# Fuente_TP1.net
KiCad netlist of a schematic drawn in Altium Designer
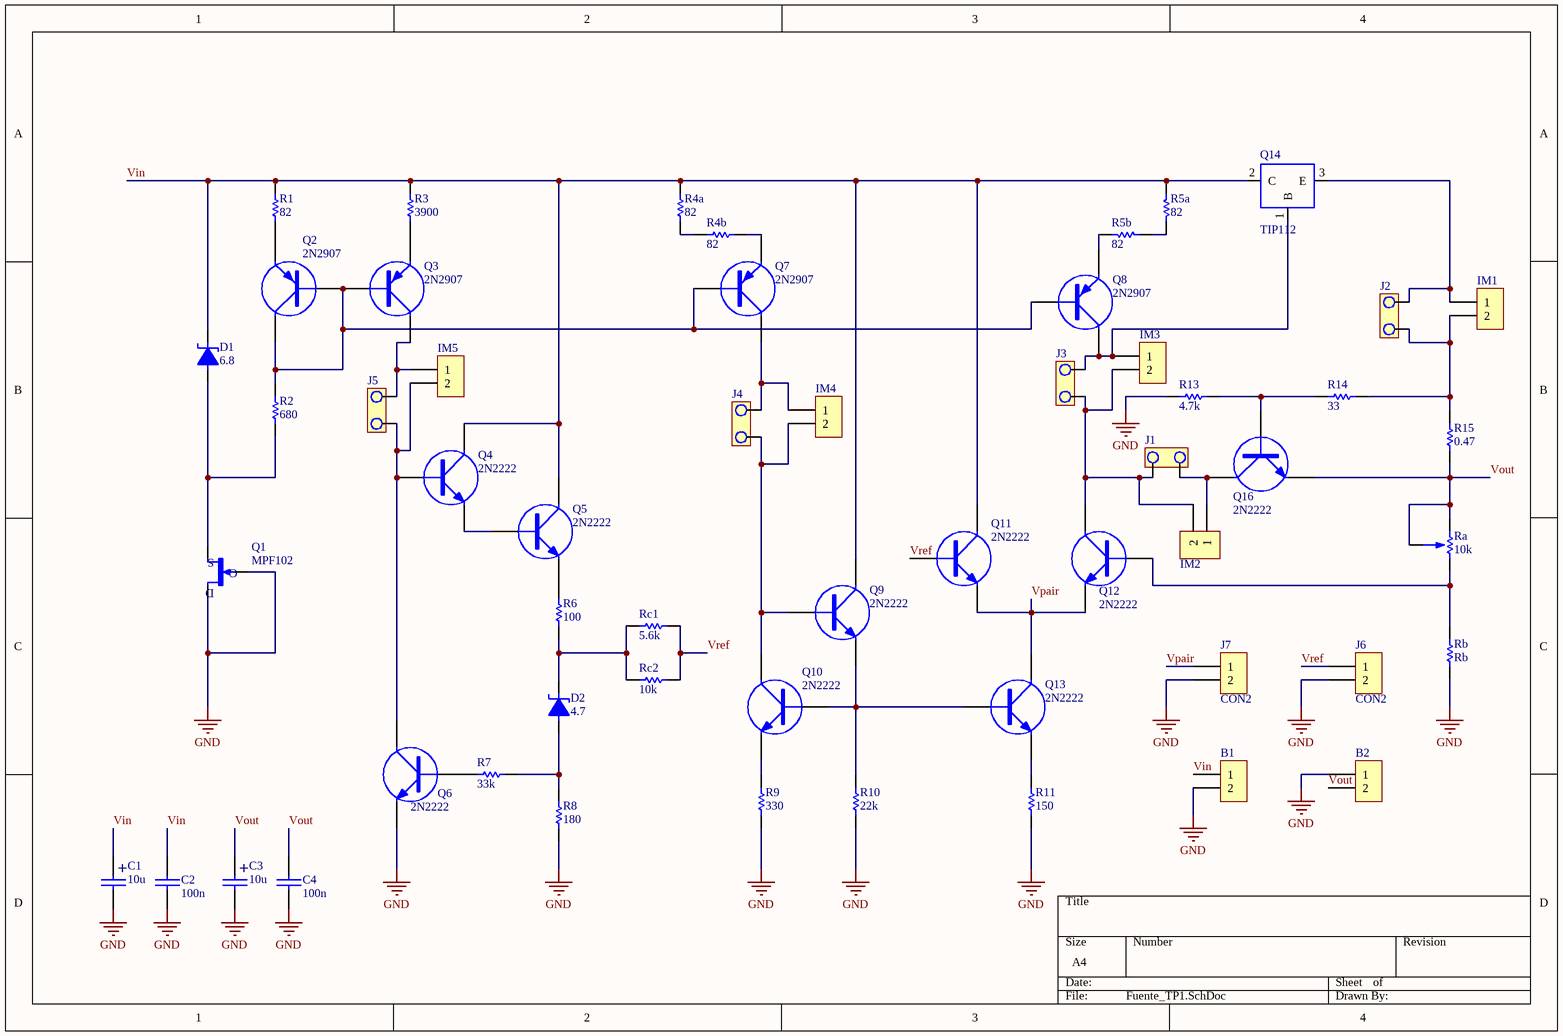
[diagram p0: Fuente_TP1.SchDoc]

(export (version "E")
  (design (tool "Eeschema 10.0.6"))
  (components
    (comp (ref "B1") (value "~") (footprint "BORNERA2") (libsource (lib "Schematics") (part "BORNERA 2")))
    (comp (ref "B2") (value "~") (footprint "BORNERA2") (libsource (lib "Schematics") (part "BORNERA 2")))
    (comp (ref "C1") (value "10u") (footprint "CAP100RP") (libsource (lib "Schematics") (part "CAPPOL")))
    (comp (ref "C2") (value "100n") (footprint "CAP200") (libsource (lib "Schematics") (part "CAP")))
    (comp (ref "C3") (value "10u") (footprint "CAP100RP") (libsource (lib "Schematics") (part "CAPPOL")))
    (comp (ref "C4") (value "100n") (footprint "CAP200") (libsource (lib "Schematics") (part "CAP")))
    (comp (ref "D1") (value "6.8") (footprint "DO41") (libsource (lib "Schematics") (part "DIODO ZENER")))
    (comp (ref "D2") (value "4.7") (footprint "DO41") (libsource (lib "Schematics") (part "DIODO ZENER")))
    (comp (ref "IM1") (value "~") (footprint "SIP2") (libsource (lib "Schematics") (part "CON2")))
    (comp (ref "IM2") (value "~") (footprint "SIP2") (libsource (lib "") (part "CON2_1")))
    (comp (ref "IM3") (value "~") (footprint "SIP2") (libsource (lib "Schematics") (part "CON2")))
    (comp (ref "IM4") (value "~") (footprint "SIP2") (libsource (lib "Schematics") (part "CON2")))
    (comp (ref "IM5") (value "~") (footprint "SIP2") (libsource (lib "Schematics") (part "CON2")))
    (comp (ref "J1") (value "~") (footprint "JUMPER2") (libsource (lib "Schematics") (part "JUMPER")))
    (comp (ref "J2") (value "~") (footprint "JUMPER2") (libsource (lib "") (part "JUMPER_1")))
    (comp (ref "J3") (value "~") (footprint "JUMPER2") (libsource (lib "") (part "JUMPER_1")))
    (comp (ref "J4") (value "~") (footprint "JUMPER2") (libsource (lib "") (part "JUMPER_1")))
    (comp (ref "J5") (value "~") (footprint "JUMPER2") (libsource (lib "") (part "JUMPER_1")))
    (comp (ref "J6") (value "CON2") (footprint "SIP2") (libsource (lib "Schematics") (part "CON2")))
    (comp (ref "J7") (value "CON2") (footprint "SIP2") (libsource (lib "Schematics") (part "CON2")))
    (comp (ref "Q1")
      (value "MPF102")
      (footprint "Footprints:TO92")
      (description "RF Mosfet N-Channel JFET TO-92-3")
      (fields (field (name "MF") "ON Semiconductor"))
      (libsource (lib "Schematics") (part "MPF102"))
    )
    (comp (ref "Q2")
      (value "2N2907")
      (footprint "TO92")
      (libsource (lib "Schematics") (part "TRANSISTOR PNP"))
    )
    (comp (ref "Q3")
      (value "2N2907")
      (footprint "TO92")
      (libsource (lib "Schematics") (part "TRANSISTOR PNP"))
    )
    (comp (ref "Q4") (value "2N2222") (footprint "TO92") (libsource (lib "Schematics") (part "2N2222")))
    (comp (ref "Q5") (value "2N2222") (footprint "TO92") (libsource (lib "Schematics") (part "2N2222")))
    (comp (ref "Q6") (value "2N2222") (footprint "TO92") (libsource (lib "Schematics") (part "2N2222")))
    (comp (ref "Q7")
      (value "2N2907")
      (footprint "TO92")
      (libsource (lib "Schematics") (part "TRANSISTOR PNP"))
    )
    (comp (ref "Q8")
      (value "2N2907")
      (footprint "TO92")
      (libsource (lib "Schematics") (part "TRANSISTOR PNP"))
    )
    (comp (ref "Q9") (value "2N2222") (footprint "TO92") (libsource (lib "Schematics") (part "2N2222")))
    (comp (ref "Q10") (value "2N2222") (footprint "TO92") (libsource (lib "Schematics") (part "2N2222")))
    (comp (ref "Q11") (value "2N2222") (footprint "TO92") (libsource (lib "Schematics") (part "2N2222")))
    (comp (ref "Q12") (value "2N2222") (footprint "TO92") (libsource (lib "Schematics") (part "2N2222")))
    (comp (ref "Q13") (value "2N2222") (footprint "TO92") (libsource (lib "Schematics") (part "2N2222")))
    (comp (ref "Q14")
      (value "TIP112")
      (footprint "Footprints:TO-220 V")
      (libsource (lib "Schematics") (part "TIP112"))
    )
    (comp (ref "Q16") (value "2N2222") (footprint "TO92") (libsource (lib "Schematics") (part "2N2222")))
    (comp (ref "R1") (value "82") (footprint "0805") (libsource (lib "Schematics") (part "RES")))
    (comp (ref "R2") (value "680") (footprint "0805") (libsource (lib "Schematics") (part "RES")))
    (comp (ref "R3") (value "3900") (footprint "0805") (libsource (lib "Schematics") (part "RES")))
    (comp (ref "R4a") (value "82") (footprint "0805") (libsource (lib "Schematics") (part "RES")))
    (comp (ref "R4b") (value "82") (footprint "0805") (libsource (lib "Schematics") (part "RES")))
    (comp (ref "R5a") (value "82") (footprint "0805") (libsource (lib "Schematics") (part "RES")))
    (comp (ref "R5b") (value "82") (footprint "0805") (libsource (lib "Schematics") (part "RES")))
    (comp (ref "R6") (value "100") (footprint "RES300") (libsource (lib "Schematics") (part "RES")))
    (comp (ref "R7") (value "33k") (footprint "0805") (libsource (lib "Schematics") (part "RES")))
    (comp (ref "R8") (value "180") (footprint "RES300") (libsource (lib "Schematics") (part "RES")))
    (comp (ref "R9") (value "330") (footprint "0805") (libsource (lib "Schematics") (part "RES")))
    (comp (ref "R10") (value "22k") (footprint "0805") (libsource (lib "Schematics") (part "RES")))
    (comp (ref "R11") (value "150") (footprint "0805") (libsource (lib "Schematics") (part "RES")))
    (comp (ref "R13") (value "4.7k") (footprint "0805") (libsource (lib "Schematics") (part "RES")))
    (comp (ref "R14") (value "33") (footprint "0805") (libsource (lib "Schematics") (part "RES")))
    (comp (ref "R15") (value "0.47") (footprint "RES600") (libsource (lib "Schematics") (part "RES")))
    (comp (ref "Ra") (value "10k") (footprint "PRESET V") (libsource (lib "Schematics") (part "PRESET")))
    (comp (ref "Rb") (value "Rb") (footprint "0805") (libsource (lib "Schematics") (part "RES")))
    (comp (ref "Rc1") (value "5.6k") (footprint "0805") (libsource (lib "Schematics") (part "RES")))
    (comp (ref "Rc2") (value "10k") (footprint "0805") (libsource (lib "Schematics") (part "RES")))
  )
  (nets
    (net (code "1") (name "/Vin") (class "Default")
      (node (ref "B1") (pin "1") (pinfunction "1_1") (pintype "passive"))
      (node (ref "C1") (pin "1") (pinfunction "1_1") (pintype "passive"))
      (node (ref "C2") (pin "1") (pinfunction "1_1") (pintype "passive"))
      (node (ref "D1") (pin "2") (pinfunction "2_2") (pintype "passive"))
      (node (ref "Q11") (pin "3") (pinfunction "C_3") (pintype "passive"))
      (node (ref "Q14") (pin "2") (pinfunction "C_2") (pintype "bidirectional"))
      (node (ref "Q4") (pin "3") (pinfunction "C_3") (pintype "passive"))
      (node (ref "Q5") (pin "3") (pinfunction "C_3") (pintype "passive"))
      (node (ref "Q9") (pin "3") (pinfunction "C_3") (pintype "passive"))
      (node (ref "R1") (pin "2") (pinfunction "2_2") (pintype "passive"))
      (node (ref "R3") (pin "2") (pinfunction "2_2") (pintype "passive"))
      (node (ref "R4a") (pin "1") (pinfunction "1_1") (pintype "passive"))
      (node (ref "R5a") (pin "1") (pinfunction "1_1") (pintype "passive"))
    )
    (net (code "2") (name "/Vout") (class "Default")
      (node (ref "B2") (pin "2") (pinfunction "2_2") (pintype "passive"))
      (node (ref "C3") (pin "1") (pinfunction "1_1") (pintype "passive"))
      (node (ref "C4") (pin "1") (pinfunction "1_1") (pintype "passive"))
      (node (ref "Q16") (pin "2") (pinfunction "E_2") (pintype "passive"))
      (node (ref "R15") (pin "1") (pinfunction "1_1") (pintype "passive"))
      (node (ref "Ra") (pin "2") (pinfunction "2_2") (pintype "passive"))
      (node (ref "Ra") (pin "3") (pinfunction "3_3") (pintype "passive"))
    )
    (net (code "3") (name "/Vpair") (class "Default")
      (node (ref "J7") (pin "1") (pinfunction "1_1") (pintype "passive"))
      (node (ref "Q11") (pin "2") (pinfunction "E_2") (pintype "passive"))
      (node (ref "Q12") (pin "2") (pinfunction "E_2") (pintype "passive"))
      (node (ref "Q13") (pin "3") (pinfunction "C_3") (pintype "passive"))
    )
    (net (code "4") (name "/Vref") (class "Default")
      (node (ref "J6") (pin "1") (pinfunction "1_1") (pintype "passive"))
      (node (ref "Q11") (pin "1") (pinfunction "B_1") (pintype "passive"))
      (node (ref "Rc1") (pin "1") (pinfunction "1_1") (pintype "passive"))
      (node (ref "Rc2") (pin "1") (pinfunction "1_1") (pintype "passive"))
    )
    (net (code "5") (name "GND") (class "Default")
      (node (ref "B1") (pin "2") (pinfunction "2_2") (pintype "passive"))
      (node (ref "B2") (pin "1") (pinfunction "1_1") (pintype "passive"))
      (node (ref "C1") (pin "2") (pinfunction "2_2") (pintype "passive"))
      (node (ref "C2") (pin "2") (pinfunction "2_2") (pintype "passive"))
      (node (ref "C3") (pin "2") (pinfunction "2_2") (pintype "passive"))
      (node (ref "C4") (pin "2") (pinfunction "2_2") (pintype "passive"))
      (node (ref "J6") (pin "2") (pinfunction "2_2") (pintype "passive"))
      (node (ref "J7") (pin "2") (pinfunction "2_2") (pintype "passive"))
      (node (ref "Q1") (pin "1") (pinfunction "D_1") (pintype "passive"))
      (node (ref "Q1") (pin "3") (pinfunction "G_3") (pintype "passive"))
      (node (ref "Q6") (pin "2") (pinfunction "E_2") (pintype "passive"))
      (node (ref "R10") (pin "2") (pinfunction "2_2") (pintype "passive"))
      (node (ref "R11") (pin "2") (pinfunction "2_2") (pintype "passive"))
      (node (ref "R13") (pin "2") (pinfunction "2_2") (pintype "passive"))
      (node (ref "R8") (pin "2") (pinfunction "2_2") (pintype "passive"))
      (node (ref "R9") (pin "2") (pinfunction "2_2") (pintype "passive"))
      (node (ref "Rb") (pin "1") (pinfunction "1_1") (pintype "passive"))
    )
    (net (code "6") (name "Net-(D2-Pad1)") (class "Default")
      (node (ref "D2") (pin "1") (pinfunction "1_1") (pintype "passive"))
      (node (ref "R7") (pin "1") (pinfunction "1_1") (pintype "passive"))
      (node (ref "R8") (pin "1") (pinfunction "1_1") (pintype "passive"))
    )
    (net (code "7") (name "Net-(D2-Pad2)") (class "Default")
      (node (ref "D2") (pin "2") (pinfunction "2_2") (pintype "passive"))
      (node (ref "R6") (pin "1") (pinfunction "1_1") (pintype "passive"))
      (node (ref "Rc1") (pin "2") (pinfunction "2_2") (pintype "passive"))
      (node (ref "Rc2") (pin "2") (pinfunction "2_2") (pintype "passive"))
    )
    (net (code "8") (name "Net-(IM1-Pad2)") (class "Default")
      (node (ref "IM1") (pin "2") (pinfunction "2_2") (pintype "passive"))
      (node (ref "J2") (pin "2") (pinfunction "2_2") (pintype "passive"))
      (node (ref "R14") (pin "1") (pinfunction "1_1") (pintype "passive"))
      (node (ref "R15") (pin "2") (pinfunction "2_2") (pintype "passive"))
    )
    (net (code "9") (name "Net-(Q1-S)") (class "Default")
      (node (ref "D1") (pin "1") (pinfunction "1_1") (pintype "passive"))
      (node (ref "Q1") (pin "2") (pinfunction "S_2") (pintype "passive"))
      (node (ref "R2") (pin "1") (pinfunction "1_1") (pintype "passive"))
    )
    (net (code "10") (name "Net-(Q2-B)") (class "Default")
      (node (ref "Q2") (pin "1") (pinfunction "B_1") (pintype "passive"))
      (node (ref "Q2") (pin "2") (pinfunction "C_2") (pintype "passive"))
      (node (ref "Q3") (pin "1") (pinfunction "B_1") (pintype "passive"))
      (node (ref "Q7") (pin "1") (pinfunction "B_1") (pintype "passive"))
      (node (ref "Q8") (pin "1") (pinfunction "B_1") (pintype "passive"))
      (node (ref "R2") (pin "2") (pinfunction "2_2") (pintype "passive"))
    )
    (net (code "11") (name "Net-(Q2-E)") (class "Default")
      (node (ref "Q2") (pin "3") (pinfunction "E_3") (pintype "passive"))
      (node (ref "R1") (pin "1") (pinfunction "1_1") (pintype "passive"))
    )
    (net (code "12") (name "Net-(Q3-C)") (class "Default")
      (node (ref "IM5") (pin "1") (pinfunction "1_1") (pintype "passive"))
      (node (ref "J5") (pin "1") (pinfunction "1_1") (pintype "passive"))
      (node (ref "Q3") (pin "2") (pinfunction "C_2") (pintype "passive"))
    )
    (net (code "13") (name "Net-(Q3-E)") (class "Default")
      (node (ref "Q3") (pin "3") (pinfunction "E_3") (pintype "passive"))
      (node (ref "R3") (pin "1") (pinfunction "1_1") (pintype "passive"))
    )
    (net (code "14") (name "Net-(Q4-B)") (class "Default")
      (node (ref "IM5") (pin "2") (pinfunction "2_2") (pintype "passive"))
      (node (ref "J5") (pin "2") (pinfunction "2_2") (pintype "passive"))
      (node (ref "Q4") (pin "1") (pinfunction "B_1") (pintype "passive"))
      (node (ref "Q6") (pin "3") (pinfunction "C_3") (pintype "passive"))
    )
    (net (code "15") (name "Net-(Q4-E)") (class "Default")
      (node (ref "Q4") (pin "2") (pinfunction "E_2") (pintype "passive"))
      (node (ref "Q5") (pin "1") (pinfunction "B_1") (pintype "passive"))
    )
    (net (code "16") (name "Net-(Q5-E)") (class "Default")
      (node (ref "Q5") (pin "2") (pinfunction "E_2") (pintype "passive"))
      (node (ref "R6") (pin "2") (pinfunction "2_2") (pintype "passive"))
    )
    (net (code "17") (name "Net-(Q6-B)") (class "Default")
      (node (ref "Q6") (pin "1") (pinfunction "B_1") (pintype "passive"))
      (node (ref "R7") (pin "2") (pinfunction "2_2") (pintype "passive"))
    )
    (net (code "18") (name "Net-(Q7-C)") (class "Default")
      (node (ref "IM4") (pin "1") (pinfunction "1_1") (pintype "passive"))
      (node (ref "J4") (pin "1") (pinfunction "1_1") (pintype "passive"))
      (node (ref "Q7") (pin "2") (pinfunction "C_2") (pintype "passive"))
    )
    (net (code "19") (name "Net-(Q7-E)") (class "Default")
      (node (ref "Q7") (pin "3") (pinfunction "E_3") (pintype "passive"))
      (node (ref "R4b") (pin "1") (pinfunction "1_1") (pintype "passive"))
    )
    (net (code "20") (name "Net-(Q8-E)") (class "Default")
      (node (ref "Q8") (pin "3") (pinfunction "E_3") (pintype "passive"))
      (node (ref "R5b") (pin "1") (pinfunction "1_1") (pintype "passive"))
    )
    (net (code "21") (name "Net-(Q10-B)") (class "Default")
      (node (ref "Q10") (pin "1") (pinfunction "B_1") (pintype "passive"))
      (node (ref "Q13") (pin "1") (pinfunction "B_1") (pintype "passive"))
      (node (ref "Q9") (pin "2") (pinfunction "E_2") (pintype "passive"))
      (node (ref "R10") (pin "1") (pinfunction "1_1") (pintype "passive"))
    )
    (net (code "22") (name "Net-(Q10-C)") (class "Default")
      (node (ref "IM4") (pin "2") (pinfunction "2_2") (pintype "passive"))
      (node (ref "J4") (pin "2") (pinfunction "2_2") (pintype "passive"))
      (node (ref "Q10") (pin "3") (pinfunction "C_3") (pintype "passive"))
      (node (ref "Q9") (pin "1") (pinfunction "B_1") (pintype "passive"))
    )
    (net (code "23") (name "Net-(Q10-E)") (class "Default")
      (node (ref "Q10") (pin "2") (pinfunction "E_2") (pintype "passive"))
      (node (ref "R9") (pin "1") (pinfunction "1_1") (pintype "passive"))
    )
    (net (code "24") (name "Net-(Q12-B)") (class "Default")
      (node (ref "Q12") (pin "1") (pinfunction "B_1") (pintype "passive"))
      (node (ref "Ra") (pin "1") (pinfunction "1_1") (pintype "passive"))
      (node (ref "Rb") (pin "2") (pinfunction "2_2") (pintype "passive"))
    )
    (net (code "25") (name "Net-(Q12-C)") (class "Default")
      (node (ref "IM2") (pin "2") (pinfunction "2_2") (pintype "passive"))
      (node (ref "IM3") (pin "2") (pinfunction "2_2") (pintype "passive"))
      (node (ref "J1") (pin "2") (pinfunction "2_2") (pintype "passive"))
      (node (ref "J3") (pin "2") (pinfunction "2_2") (pintype "passive"))
      (node (ref "Q12") (pin "3") (pinfunction "C_3") (pintype "passive"))
    )
    (net (code "26") (name "Net-(Q13-E)") (class "Default")
      (node (ref "Q13") (pin "2") (pinfunction "E_2") (pintype "passive"))
      (node (ref "R11") (pin "1") (pinfunction "1_1") (pintype "passive"))
    )
    (net (code "27") (name "Net-(Q14-B)") (class "Default")
      (node (ref "IM3") (pin "1") (pinfunction "1_1") (pintype "passive"))
      (node (ref "J3") (pin "1") (pinfunction "1_1") (pintype "passive"))
      (node (ref "Q14") (pin "1") (pinfunction "B_1") (pintype "bidirectional"))
      (node (ref "Q8") (pin "2") (pinfunction "C_2") (pintype "passive"))
    )
    (net (code "28") (name "Net-(Q14-E)") (class "Default")
      (node (ref "IM1") (pin "1") (pinfunction "1_1") (pintype "passive"))
      (node (ref "J2") (pin "1") (pinfunction "1_1") (pintype "passive"))
      (node (ref "Q14") (pin "3") (pinfunction "E_3") (pintype "bidirectional"))
    )
    (net (code "29") (name "Net-(Q16-B)") (class "Default")
      (node (ref "Q16") (pin "1") (pinfunction "B_1") (pintype "passive"))
      (node (ref "R13") (pin "1") (pinfunction "1_1") (pintype "passive"))
      (node (ref "R14") (pin "2") (pinfunction "2_2") (pintype "passive"))
    )
    (net (code "30") (name "Net-(Q16-C)") (class "Default")
      (node (ref "IM2") (pin "1") (pinfunction "1_1") (pintype "passive"))
      (node (ref "J1") (pin "1") (pinfunction "1_1") (pintype "passive"))
      (node (ref "Q16") (pin "3") (pinfunction "C_3") (pintype "passive"))
    )
    (net (code "31") (name "Net-(R4a-Pad2)") (class "Default")
      (node (ref "R4a") (pin "2") (pinfunction "2_2") (pintype "passive"))
      (node (ref "R4b") (pin "2") (pinfunction "2_2") (pintype "passive"))
    )
    (net (code "32") (name "Net-(R5a-Pad2)") (class "Default")
      (node (ref "R5a") (pin "2") (pinfunction "2_2") (pintype "passive"))
      (node (ref "R5b") (pin "2") (pinfunction "2_2") (pintype "passive"))
    )
  )
)
